# IN196CurrentSenseV2.net
KiCad netlist of a schematic drawn in EAGLE
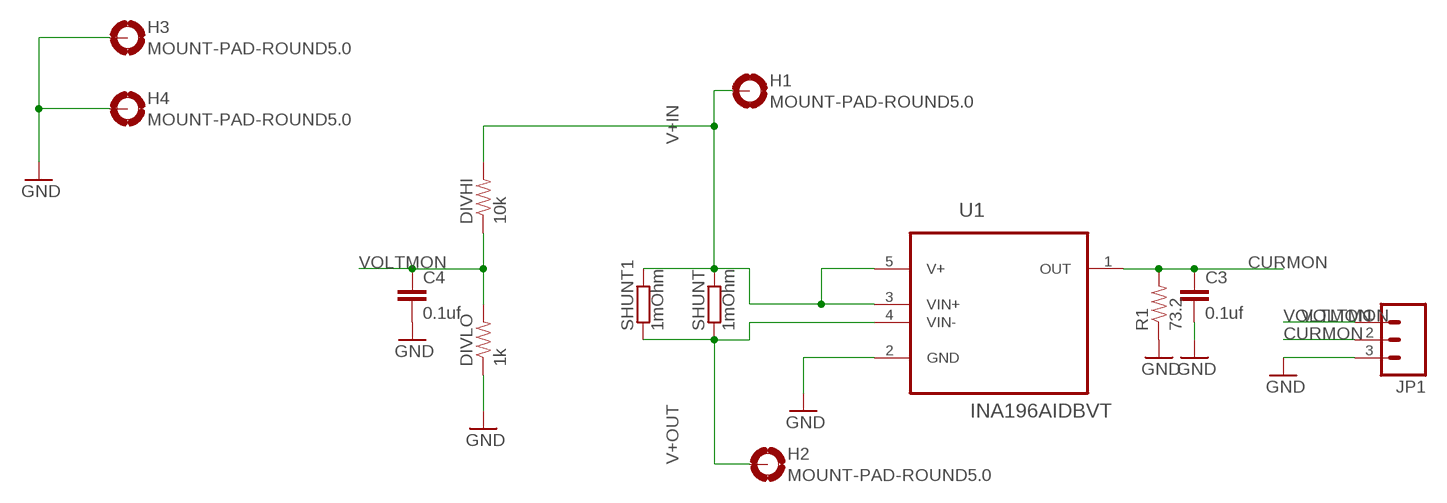
[diagram p0: schematic, sheet 1]

(export (version "E")
  (design (tool "Eeschema 10.0.6"))
  (components
    (comp (ref "C3")
      (value "0.1uf")
      (footprint "eagle-import:0603-CAP")
      (libsource (lib "eagle-import") (part "CAP0603-CAP"))
    )
    (comp (ref "C4")
      (value "0.1uf")
      (footprint "eagle-import:0603-CAP")
      (libsource (lib "eagle-import") (part "CAP0603-CAP"))
    )
    (comp (ref "DIVHI")
      (value "10k")
      (footprint "eagle-import:0603-RES")
      (libsource (lib "eagle-import") (part "RESISTOR0603"))
    )
    (comp (ref "DIVLO")
      (value "1k")
      (footprint "eagle-import:0603-RES")
      (libsource (lib "eagle-import") (part "RESISTOR0603"))
    )
    (comp (ref "H1")
      (value "MOUNT-PAD-ROUND5.0")
      (footprint "eagle-import:5,0-PAD")
      (libsource (lib "eagle-import") (part "MOUNT-PAD-ROUND5.0"))
    )
    (comp (ref "H2")
      (value "MOUNT-PAD-ROUND5.0")
      (footprint "eagle-import:5,0-PAD")
      (libsource (lib "eagle-import") (part "MOUNT-PAD-ROUND5.0"))
    )
    (comp (ref "H3")
      (value "MOUNT-PAD-ROUND5.0")
      (footprint "eagle-import:5,0-PAD")
      (libsource (lib "eagle-import") (part "MOUNT-PAD-ROUND5.0"))
    )
    (comp (ref "H4")
      (value "MOUNT-PAD-ROUND5.0")
      (footprint "eagle-import:5,0-PAD")
      (libsource (lib "eagle-import") (part "MOUNT-PAD-ROUND5.0"))
    )
    (comp (ref "JP1")
      (value "M03LONGPADS")
      (footprint "eagle-import:1X03_LONGPADS")
      (libsource (lib "eagle-import") (part "M03LONGPADS"))
    )
    (comp (ref "R1")
      (value "73.2")
      (footprint "eagle-import:0603-RES")
      (libsource (lib "eagle-import") (part "RESISTOR0603-RES"))
    )
    (comp (ref "SHUNT")
      (value "1mOhm")
      (footprint "eagle-import:SMS-0")
      (libsource (lib "eagle-import") (part "SMS-0"))
    )
    (comp (ref "SHUNT1")
      (value "1mOhm")
      (footprint "eagle-import:SMS-0")
      (libsource (lib "eagle-import") (part "SMS-0"))
    )
    (comp (ref "U1")
      (value "INA196AIDBVT")
      (footprint "eagle-import:SOT95P280X145-5N")
      (libsource (lib "eagle-import") (part "INA196AIDBVT"))
    )
  )
  (nets
    (net (code "1") (name "/CURMON") (class "Default")
      (node (ref "C3") (pin "1") (pinfunction "1_1") (pintype "passive"))
      (node (ref "JP1") (pin "2") (pinfunction "2_2") (pintype "passive"))
      (node (ref "R1") (pin "2") (pinfunction "2_2") (pintype "passive"))
      (node (ref "U1") (pin "1") (pinfunction "OUT_1") (pintype "output"))
    )
    (net (code "2") (name "/V+IN") (class "Default")
      (node (ref "DIVHI") (pin "2") (pinfunction "2_2") (pintype "passive"))
      (node (ref "H1") (pin "B5") (pinfunction "MOUNT_B5") (pintype "passive"))
      (node (ref "SHUNT") (pin "1") (pinfunction "1_1") (pintype "passive"))
      (node (ref "SHUNT1") (pin "1") (pinfunction "1_1") (pintype "passive"))
      (node (ref "U1") (pin "3") (pinfunction "VIN+_3") (pintype "input"))
      (node (ref "U1") (pin "5") (pinfunction "V+_5") (pintype "power_in"))
    )
    (net (code "3") (name "/V+OUT") (class "Default")
      (node (ref "H2") (pin "B5") (pinfunction "MOUNT_B5") (pintype "passive"))
      (node (ref "SHUNT") (pin "2") (pinfunction "2_2") (pintype "passive"))
      (node (ref "SHUNT1") (pin "2") (pinfunction "2_2") (pintype "passive"))
      (node (ref "U1") (pin "4") (pinfunction "VIN-_4") (pintype "input"))
    )
    (net (code "4") (name "/VOLTMON") (class "Default")
      (node (ref "C4") (pin "1") (pinfunction "1_1") (pintype "passive"))
      (node (ref "DIVHI") (pin "1") (pinfunction "1_1") (pintype "passive"))
      (node (ref "DIVLO") (pin "2") (pinfunction "2_2") (pintype "passive"))
      (node (ref "JP1") (pin "1") (pinfunction "1_1") (pintype "passive"))
    )
    (net (code "5") (name "GND") (class "Default")
      (node (ref "C3") (pin "2") (pinfunction "2_2") (pintype "passive"))
      (node (ref "C4") (pin "2") (pinfunction "2_2") (pintype "passive"))
      (node (ref "DIVLO") (pin "1") (pinfunction "1_1") (pintype "passive"))
      (node (ref "H3") (pin "B5") (pinfunction "MOUNT_B5") (pintype "passive"))
      (node (ref "H4") (pin "B5") (pinfunction "MOUNT_B5") (pintype "passive"))
      (node (ref "JP1") (pin "3") (pinfunction "3_3") (pintype "passive"))
      (node (ref "R1") (pin "1") (pinfunction "1_1") (pintype "passive"))
      (node (ref "U1") (pin "2") (pinfunction "GND_2") (pintype "passive"))
    )
  )
)
